# Candunio.net
KiCad netlist of a schematic drawn in Altium Designer
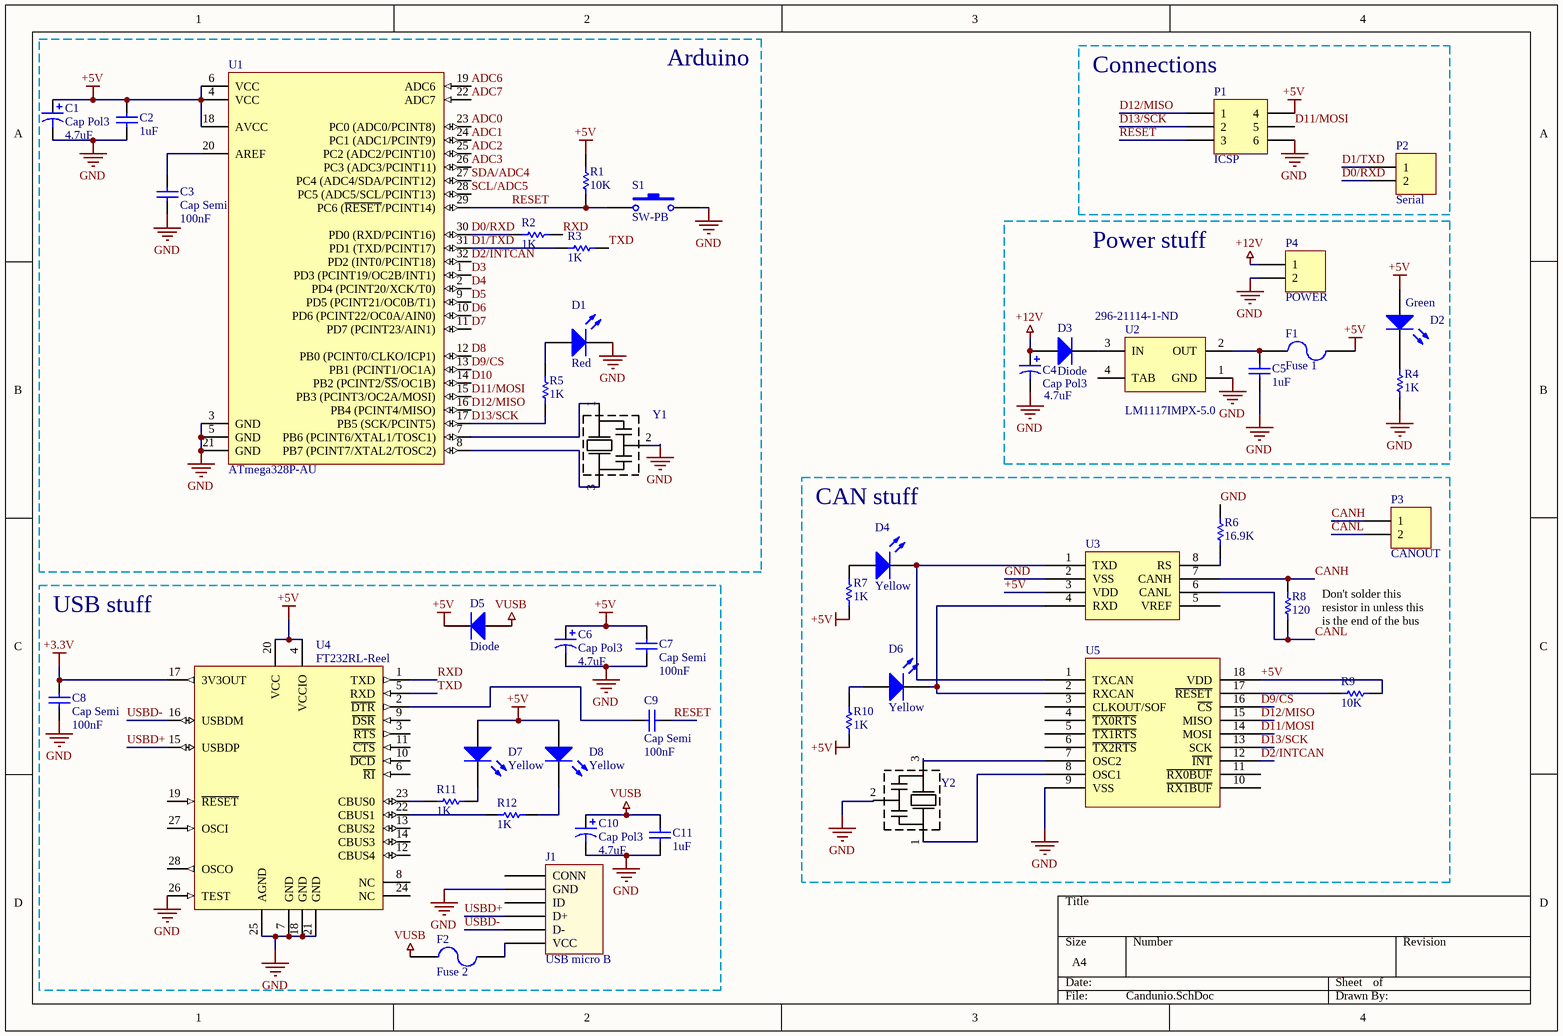
[diagram p0: Candunio.SchDoc]

(export (version "E")
  (design (tool "Eeschema 10.0.6"))
  (components
    (comp (ref "C1")
      (value "Cap Pol3")
      (footprint "CAPC3216X170N")
      (description "Polarized Capacitor (Surface Mount)")
      (fields
        (field (name "ALTIUM_VALUE") "4.7uF")
        (field (name "MANUFACTURER") "Kyocera AVX")
        (field (name "MANUFACTURER PART NUMBER") "12063C475KAT2A")
        (field (name "PUBLISHER") "Altium Limited")
      )
      (libsource (lib "Miscellaneous Devices") (part "Cap Pol3"))
    )
    (comp (ref "C2")
      (value "1uF")
      (footprint "CAPC3216X170N")
      (description "Capacitor (Semiconductor SIM Model)")
      (fields
        (field (name "MANUFACTURER") "Murata")
        (field (name "MANUFACTURER PART NUMBER") "GRM31MR71H105KA88L")
        (field (name "PUBLISHER") "Altium Limited")
      )
      (libsource (lib "Miscellaneous Devices") (part "Cap Semi"))
    )
    (comp (ref "C3")
      (value "Cap Semi")
      (footprint "CAPC3216X170N")
      (description "Capacitor (Semiconductor SIM Model)")
      (fields
        (field (name "ALTIUM_VALUE") "100nF")
        (field (name "MANUFACTURER") "Yageo")
        (field (name "MANUFACTURER PART NUMBER") "CC1206KKX7R0BB104")
        (field (name "PUBLISHER") "Altium Limited")
      )
      (libsource (lib "Miscellaneous Devices") (part "Cap Semi"))
    )
    (comp (ref "C4")
      (value "Cap Pol3")
      (footprint "CAPC3216X170N")
      (description "Polarized Capacitor (Surface Mount)")
      (fields
        (field (name "ALTIUM_VALUE") "4.7uF")
        (field (name "MANUFACTURER") "Kyocera AVX")
        (field (name "MANUFACTURER PART NUMBER") "12063C475KAT2A")
        (field (name "PUBLISHER") "Altium Limited")
      )
      (libsource (lib "Miscellaneous Devices") (part "Cap Pol3"))
    )
    (comp (ref "C5")
      (value "1uF")
      (footprint "CAPC3216X170N")
      (description "Capacitor (Semiconductor SIM Model)")
      (fields
        (field (name "MANUFACTURER") "Murata")
        (field (name "MANUFACTURER PART NUMBER") "GRM31MR71H105KA88L")
        (field (name "PUBLISHER") "Altium Limited")
      )
      (libsource (lib "Miscellaneous Devices") (part "Cap Semi"))
    )
    (comp (ref "C6")
      (value "Cap Pol3")
      (footprint "CAPC3216X170N")
      (description "Polarized Capacitor (Surface Mount)")
      (fields
        (field (name "ALTIUM_VALUE") "4.7uF")
        (field (name "MANUFACTURER") "Kyocera AVX")
        (field (name "MANUFACTURER PART NUMBER") "12063C475KAT2A")
        (field (name "PUBLISHER") "Altium Limited")
      )
      (libsource (lib "Miscellaneous Devices") (part "Cap Pol3"))
    )
    (comp (ref "C7")
      (value "Cap Semi")
      (footprint "CAPC3216X170N")
      (description "Capacitor (Semiconductor SIM Model)")
      (fields
        (field (name "ALTIUM_VALUE") "100nF")
        (field (name "MANUFACTURER") "Yageo")
        (field (name "MANUFACTURER PART NUMBER") "CC1206KKX7R0BB104")
        (field (name "PUBLISHER") "Altium Limited")
      )
      (libsource (lib "Miscellaneous Devices") (part "Cap Semi"))
    )
    (comp (ref "C8")
      (value "Cap Semi")
      (footprint "CAPC3216X170N")
      (description "Capacitor (Semiconductor SIM Model)")
      (fields
        (field (name "ALTIUM_VALUE") "100nF")
        (field (name "MANUFACTURER") "Yageo")
        (field (name "MANUFACTURER PART NUMBER") "CC1206KKX7R0BB104")
        (field (name "PUBLISHER") "Altium Limited")
      )
      (libsource (lib "Miscellaneous Devices") (part "Cap Semi"))
    )
    (comp (ref "C9")
      (value "Cap Semi")
      (footprint "CAPC3216X170N")
      (description "Capacitor (Semiconductor SIM Model)")
      (fields
        (field (name "ALTIUM_VALUE") "100nF")
        (field (name "MANUFACTURER") "Yageo")
        (field (name "MANUFACTURER PART NUMBER") "CC1206KKX7R0BB104")
        (field (name "PUBLISHER") "Altium Limited")
      )
      (libsource (lib "Miscellaneous Devices") (part "Cap Semi"))
    )
    (comp (ref "C10")
      (value "Cap Pol3")
      (footprint "CAPC3216X170N")
      (description "Polarized Capacitor (Surface Mount)")
      (fields
        (field (name "ALTIUM_VALUE") "4.7uF")
        (field (name "MANUFACTURER") "Kyocera AVX")
        (field (name "MANUFACTURER PART NUMBER") "12063C475KAT2A")
        (field (name "PUBLISHER") "Altium Limited")
      )
      (libsource (lib "Miscellaneous Devices") (part "Cap Pol3"))
    )
    (comp (ref "C11")
      (value "1uF")
      (footprint "CAPC3216X170N")
      (description "Capacitor (Semiconductor SIM Model)")
      (fields
        (field (name "MANUFACTURER") "Murata")
        (field (name "MANUFACTURER PART NUMBER") "GRM31MR71H105KA88L")
        (field (name "PUBLISHER") "Altium Limited")
      )
      (libsource (lib "Miscellaneous Devices") (part "Cap Semi"))
    )
    (comp (ref "D1")
      (value "Red")
      (footprint "LEDC3216X120NRED")
      (description "Typical RED, GREEN, YELLOW, AMBER GaAs LED")
      (fields
        (field (name "MANUFACTURER") "Broadcom Avago")
        (field (name "MANUFACTURER PART NUMBER") "HSMY-C150")
        (field (name "PUBLISHER") "Altium Limited")
      )
      (libsource (lib "Miscellaneous Devices") (part "LED2"))
    )
    (comp (ref "D2")
      (value "Green")
      (footprint "LEDC3216X120NGRN")
      (description "Typical RED, GREEN, YELLOW, AMBER GaAs LED")
      (fields
        (field (name "MANUFACTURER") "Broadcom Avago")
        (field (name "MANUFACTURER PART NUMBER") "HSMG-C150")
        (field (name "PUBLISHER") "Altium Limited")
      )
      (libsource (lib "Miscellaneous Devices") (part "LED2"))
    )
    (comp (ref "D3")
      (value "Diode")
      (footprint "DO-220AA")
      (description "Default Diode")
      (fields (field (name "PUBLISHER") "Altium Limited"))
      (libsource (lib "Miscellaneous Devices") (part "Diode"))
    )
    (comp (ref "D4")
      (value "Yellow")
      (footprint "LEDC3216X120NYEL")
      (description "Typical RED, GREEN, YELLOW, AMBER GaAs LED")
      (fields
        (field (name "MANUFACTURER") "Broadcom Avago")
        (field (name "MANUFACTURER PART NUMBER") "HSMY-C150")
        (field (name "PUBLISHER") "Altium Limited")
      )
      (libsource (lib "Miscellaneous Devices") (part "LED2"))
    )
    (comp (ref "D5")
      (value "Diode")
      (footprint "DO-220AA")
      (description "Default Diode")
      (fields (field (name "PUBLISHER") "Altium Limited"))
      (libsource (lib "Miscellaneous Devices") (part "Diode"))
    )
    (comp (ref "D6")
      (value "Yellow")
      (footprint "LEDC3216X120NYEL")
      (description "Typical RED, GREEN, YELLOW, AMBER GaAs LED")
      (fields
        (field (name "MANUFACTURER") "Broadcom Avago")
        (field (name "MANUFACTURER PART NUMBER") "HSMY-C150")
        (field (name "PUBLISHER") "Altium Limited")
      )
      (libsource (lib "Miscellaneous Devices") (part "LED2"))
    )
    (comp (ref "D7")
      (value "Yellow")
      (footprint "LEDC3216X120NYEL")
      (description "Typical RED, GREEN, YELLOW, AMBER GaAs LED")
      (fields
        (field (name "MANUFACTURER") "Broadcom Avago")
        (field (name "MANUFACTURER PART NUMBER") "HSMY-C150")
        (field (name "PUBLISHER") "Altium Limited")
      )
      (libsource (lib "Miscellaneous Devices") (part "LED2"))
    )
    (comp (ref "D8")
      (value "Yellow")
      (footprint "LEDC3216X120NYEL")
      (description "Typical RED, GREEN, YELLOW, AMBER GaAs LED")
      (fields
        (field (name "MANUFACTURER") "Broadcom Avago")
        (field (name "MANUFACTURER PART NUMBER") "HSMY-C150")
        (field (name "PUBLISHER") "Altium Limited")
      )
      (libsource (lib "Miscellaneous Devices") (part "LED2"))
    )
    (comp (ref "F1")
      (value "Fuse 1")
      (footprint "FUSC4632X85N")
      (description "Fuse")
      (fields
        (field (name "PART NUMBER") "MF-MSMF050-2")
        (field (name "MANUFACTURER") "Bourns")
        (field (name "PUBLISHER") "Altium Limited")
      )
      (libsource (lib "Miscellaneous Devices") (part "Fuse 2"))
    )
    (comp (ref "F2")
      (value "Fuse 2")
      (footprint "FUSC4632X85N")
      (description "Fuse")
      (fields
        (field (name "PART NUMBER") "MF-MSMF050-2")
        (field (name "MANUFACTURER") "Bourns")
        (field (name "PUBLISHER") "Altium Limited")
      )
      (libsource (lib "Miscellaneous Devices") (part "Fuse 2"))
    )
    (comp (ref "J1")
      (value "USB micro B")
      (footprint "1050170001")
      (description "CONN SM TH USB MICRO MODIFIED FOR DRILL")
      (fields (field (name "PART NUMBER") "WM1399CT-ND"))
      (libsource (lib "electronpowered") (part "1050170001"))
    )
    (comp (ref "P1")
      (value "ICSP")
      (footprint "Pin Header 2x3 TH Pitch 2.54mm")
      (description "Header, 3-Pin, Dual row")
      (fields (field (name "PUBLISHER") "Altium Limited"))
      (libsource (lib "Miscellaneous Connectors") (part "Header 3X2A"))
    )
    (comp (ref "P2")
      (value "Serial")
      (footprint "Candunio:Pin Header 1x2 TH Pitch 2.54mm")
      (description "Header, 2-Pin")
      (fields (field (name "PUBLISHER") "Altium Limited"))
      (libsource (lib "Miscellaneous Connectors") (part "Header 2"))
    )
    (comp (ref "P3")
      (value "CANOUT")
      (footprint "Candunio:Pin Header 1x2 TH Pitch 2.54mm")
      (description "Header, 2-Pin")
      (fields (field (name "PUBLISHER") "Altium Limited"))
      (libsource (lib "Miscellaneous Connectors") (part "Header 2"))
    )
    (comp (ref "P4")
      (value "POWER")
      (footprint "Candunio:Pin Header 1x2 TH Pitch 2.54mm")
      (description "Header, 2-Pin")
      (fields (field (name "PUBLISHER") "Altium Limited"))
      (libsource (lib "Miscellaneous Connectors") (part "Header 2"))
    )
    (comp (ref "R1")
      (value "10K")
      (footprint "RESC3216X60N")
      (description "Resistor")
      (fields
        (field (name "MANUFACTURER") "Stackpole Electronics")
        (field (name "MANUFACTURER PART NUMBER") "RNCP1206FTD1K00")
      )
      (libsource (lib "Miscellaneous Devices") (part "Res1"))
    )
    (comp (ref "R2")
      (value "1K")
      (footprint "RESC3216X60N")
      (description "Resistor")
      (fields
        (field (name "MANUFACTURER") "Stackpole Electronics")
        (field (name "MANUFACTURER PART NUMBER") "RNCP1206FTD1K00")
      )
      (libsource (lib "Miscellaneous Devices") (part "Res1"))
    )
    (comp (ref "R3")
      (value "1K")
      (footprint "RESC3216X60N")
      (description "Resistor")
      (fields
        (field (name "MANUFACTURER") "Stackpole Electronics")
        (field (name "MANUFACTURER PART NUMBER") "RNCP1206FTD1K00")
      )
      (libsource (lib "Miscellaneous Devices") (part "Res1"))
    )
    (comp (ref "R4")
      (value "1K")
      (footprint "RESC3216X60N")
      (description "Resistor")
      (fields
        (field (name "MANUFACTURER") "Stackpole Electronics")
        (field (name "MANUFACTURER PART NUMBER") "RNCP1206FTD1K00")
      )
      (libsource (lib "Miscellaneous Devices") (part "Res1"))
    )
    (comp (ref "R5")
      (value "1K")
      (footprint "RESC3216X60N")
      (description "Resistor")
      (fields
        (field (name "MANUFACTURER") "Stackpole Electronics")
        (field (name "MANUFACTURER PART NUMBER") "RNCP1206FTD1K00")
      )
      (libsource (lib "Miscellaneous Devices") (part "Res1"))
    )
    (comp (ref "R6")
      (value "16.9K")
      (footprint "RESC3216X60N")
      (description "Resistor")
      (fields
        (field (name "MANUFACTURER") "TE Connectivity Holsworthy")
        (field (name "MANUFACTURER PART NUMBER") "CRGH1206F16K9")
      )
      (libsource (lib "Miscellaneous Devices") (part "Res1"))
    )
    (comp (ref "R7")
      (value "1K")
      (footprint "RESC3216X60N")
      (description "Resistor")
      (fields
        (field (name "MANUFACTURER") "Stackpole Electronics")
        (field (name "MANUFACTURER PART NUMBER") "RNCP1206FTD1K00")
      )
      (libsource (lib "Miscellaneous Devices") (part "Res1"))
    )
    (comp (ref "R8")
      (value "120")
      (footprint "RESC3216X60N")
      (description "Resistor")
      (fields
        (field (name "MANUFACTURER") "Vishay")
        (field (name "MANUFACTURER PART NUMBER") "CRCW1206120RFKEAHP")
      )
      (libsource (lib "Miscellaneous Devices") (part "Res1"))
    )
    (comp (ref "R9")
      (value "10K")
      (footprint "RESC3216X60N")
      (description "Resistor")
      (fields
        (field (name "MANUFACTURER") "Stackpole Electronics")
        (field (name "MANUFACTURER PART NUMBER") "RNCP1206FTD10K0")
      )
      (libsource (lib "Miscellaneous Devices") (part "Res1"))
    )
    (comp (ref "R10")
      (value "1K")
      (footprint "RESC3216X60N")
      (description "Resistor")
      (fields
        (field (name "MANUFACTURER") "Stackpole Electronics")
        (field (name "MANUFACTURER PART NUMBER") "RNCP1206FTD1K00")
      )
      (libsource (lib "Miscellaneous Devices") (part "Res1"))
    )
    (comp (ref "R11")
      (value "1K")
      (footprint "RESC3216X60N")
      (description "Resistor")
      (fields
        (field (name "MANUFACTURER") "Stackpole Electronics")
        (field (name "MANUFACTURER PART NUMBER") "RNCP1206FTD1K00")
      )
      (libsource (lib "Miscellaneous Devices") (part "Res1"))
    )
    (comp (ref "R12")
      (value "1K")
      (footprint "RESC3216X60N")
      (description "Resistor")
      (fields
        (field (name "MANUFACTURER") "Stackpole Electronics")
        (field (name "MANUFACTURER PART NUMBER") "RNCP1206FTD1K00")
      )
      (libsource (lib "Miscellaneous Devices") (part "Res1"))
    )
    (comp (ref "S1")
      (value "SW-PB")
      (footprint "C1206")
      (description "Switch")
      (fields
        (field (name "MANUFACTURER") "ITT C&K")
        (field (name "MANUFACTURER PART NUMBER") "KXT331LHS")
        (field (name "PUBLISHER") "Altium Limited")
      )
      (libsource (lib "Miscellaneous Devices") (part "SW-PB"))
    )
    (comp (ref "U1")
      (value "ATmega328P-AU")
      (footprint "QFP80P900X900X120-32N")
      (fields (field (name "PUBLISHER") "Altium Limited"))
      (libsource (lib "Atmel Microcontroller 8-Bit megaAVR") (part "ATmega328P-AU"))
    )
    (comp (ref "U2")
      (value "LM1117IMPX-5.0")
      (footprint "SOT230P700X180-4N")
      (description "800mA Low-Dropout Linear Regulator, 4-pin SOT-223")
      (fields
        (field (name "PARTNUMBER") "LM1117IMPX-5.0/NOPBCT-ND")
        (field (name "MANUFACTURER") "National Semiconductor")
        (field (name "SUPPLIER PART NUMBER") "296-21114-1-ND")
        (field (name "PUBLISHER") "Altium Limited")
      )
      (libsource (lib "NSC LDO") (part "LM1117IMPX-5.0"))
    )
    (comp (ref "U3")
      (value "MCP2551-E/SN")
      (footprint "SOIC127P600X175-8N")
      (description "SOIC")
      (libsource (lib "AMSComponents") (part "MCP2551-E/SN"))
    )
    (comp (ref "U4")
      (value "FT232RL-Reel")
      (footprint "SOP65P780X200-28N")
      (description "USB UART Asynchronous Serial Data Transfer Chip, SSOP-28, Tape and Reel")
      (fields
        (field (name "MANUFACTURER") "FTDI")
        (field (name "MANUFACTURER PART NUMBER") "FT232RL-REEL")
        (field (name "PUBLISHER") "Altium Limited")
      )
      (libsource (lib "FTDI Communication UART") (part "FT232RL-Reel"))
    )
    (comp (ref "U5")
      (value "MCP2515-E/ST")
      (footprint "SOIC127P1030X265-18N")
      (description "SOIC")
      (libsource (lib "AMSComponents") (part "MCP2515-E/ST"))
    )
    (comp (ref "Y1")
      (value "CSTCE16M0V53-R0")
      (footprint "CSTCE_G")
      (fields
        (field (name "MANUFACTURER") "Murata")
        (field (name "MANUFACTURER PART NUMBER") "CSTCE16M0V53C-R0")
        (field (name "TOLERANCE") "0.5%")
      )
      (libsource (lib "AMSComponents") (part "CSTCE16M0V53-R0"))
    )
    (comp (ref "Y2")
      (value "CSTCE16M0V53-R0")
      (footprint "CSTCE_G")
      (fields
        (field (name "MANUFACTURER") "Murata")
        (field (name "MANUFACTURER PART NUMBER") "CSTCE16M0V53C-R0")
        (field (name "TOLERANCE") "0.5%")
      )
      (libsource (lib "AMSComponents") (part "CSTCE16M0V53-R0"))
    )
  )
  (nets
    (net (code "1") (name "+3.3V") (class "Default")
      (node (ref "C8") (pin "1") (pinfunction "1_1") (pintype "passive"))
      (node (ref "U4") (pin "17") (pinfunction "3V3OUT_17") (pintype "output"))
    )
    (net (code "2") (name "+5V") (class "Default")
      (node (ref "C1") (pin "1") (pinfunction "1_1") (pintype "passive"))
      (node (ref "C2") (pin "1") (pinfunction "1_1") (pintype "passive"))
      (node (ref "C6") (pin "1") (pinfunction "1_1") (pintype "passive"))
      (node (ref "C7") (pin "1") (pinfunction "1_1") (pintype "passive"))
      (node (ref "D2") (pin "1") (pinfunction "A_1") (pintype "passive"))
      (node (ref "D5") (pin "1") (pinfunction "K_1") (pintype "passive"))
      (node (ref "D7") (pin "1") (pinfunction "A_1") (pintype "passive"))
      (node (ref "D8") (pin "1") (pinfunction "A_1") (pintype "passive"))
      (node (ref "F1") (pin "2") (pinfunction "2_2") (pintype "passive"))
      (node (ref "P1") (pin "4") (pinfunction "4_4") (pintype "passive"))
      (node (ref "R1") (pin "1") (pinfunction "1_1") (pintype "passive"))
      (node (ref "R10") (pin "2") (pinfunction "2_2") (pintype "passive"))
      (node (ref "R7") (pin "1") (pinfunction "1_1") (pintype "passive"))
      (node (ref "R9") (pin "2") (pinfunction "2_2") (pintype "passive"))
      (node (ref "U1") (pin "18") (pinfunction "AVCC_18") (pintype "power_in"))
      (node (ref "U1") (pin "4") (pinfunction "VCC_4") (pintype "power_in"))
      (node (ref "U1") (pin "6") (pinfunction "VCC_6") (pintype "power_in"))
      (node (ref "U3") (pin "3") (pinfunction "VDD_3") (pintype "passive"))
      (node (ref "U4") (pin "20") (pinfunction "VCC_20") (pintype "power_in"))
      (node (ref "U4") (pin "4") (pinfunction "VCCIO_4") (pintype "power_in"))
      (node (ref "U5") (pin "18") (pinfunction "VDD_18") (pintype "passive"))
    )
    (net (code "3") (name "+12V") (class "Default")
      (node (ref "C4") (pin "1") (pinfunction "1_1") (pintype "passive"))
      (node (ref "D3") (pin "2") (pinfunction "A_2") (pintype "passive"))
      (node (ref "P4") (pin "1") (pinfunction "1_1") (pintype "passive"))
    )
    (net (code "4") (name "/ADC0") (class "Default")
      (node (ref "U1") (pin "23") (pinfunction "PC0_(ADC0/PCINT8)_23") (pintype "bidirectional"))
    )
    (net (code "5") (name "/ADC1") (class "Default")
      (node (ref "U1") (pin "24") (pinfunction "PC1_(ADC1/PCINT9)_24") (pintype "bidirectional"))
    )
    (net (code "6") (name "/ADC2") (class "Default")
      (node (ref "U1") (pin "25") (pinfunction "PC2_(ADC2/PCINT10)_25") (pintype "bidirectional"))
    )
    (net (code "7") (name "/ADC3") (class "Default")
      (node (ref "U1") (pin "26") (pinfunction "PC3_(ADC3/PCINT11)_26") (pintype "bidirectional"))
    )
    (net (code "8") (name "/ADC6") (class "Default")
      (node (ref "U1") (pin "19") (pinfunction "ADC6_19") (pintype "input"))
    )
    (net (code "9") (name "/ADC7") (class "Default")
      (node (ref "U1") (pin "22") (pinfunction "ADC7_22") (pintype "input"))
    )
    (net (code "10") (name "/CANH") (class "Default")
      (node (ref "P3") (pin "1") (pinfunction "1_1") (pintype "passive"))
      (node (ref "R8") (pin "1") (pinfunction "1_1") (pintype "passive"))
      (node (ref "U3") (pin "7") (pinfunction "CANH_7") (pintype "passive"))
    )
    (net (code "11") (name "/CANL") (class "Default")
      (node (ref "P3") (pin "2") (pinfunction "2_2") (pintype "passive"))
      (node (ref "R8") (pin "2") (pinfunction "2_2") (pintype "passive"))
      (node (ref "U3") (pin "6") (pinfunction "CANL_6") (pintype "passive"))
    )
    (net (code "12") (name "/D0{slash}RXD") (class "Default")
      (node (ref "P2") (pin "2") (pinfunction "2_2") (pintype "passive"))
      (node (ref "R2") (pin "1") (pinfunction "1_1") (pintype "passive"))
      (node (ref "U1") (pin "30") (pinfunction "PD0_(RXD/PCINT16)_30") (pintype "bidirectional"))
    )
    (net (code "13") (name "/D1{slash}TXD") (class "Default")
      (node (ref "P2") (pin "1") (pinfunction "1_1") (pintype "passive"))
      (node (ref "R3") (pin "1") (pinfunction "1_1") (pintype "passive"))
      (node (ref "U1") (pin "31") (pinfunction "PD1_(TXD/PCINT17)_31") (pintype "bidirectional"))
    )
    (net (code "14") (name "/D2{slash}INTCAN") (class "Default")
      (node (ref "U1") (pin "32") (pinfunction "PD2_(INT0/PCINT18)_32") (pintype "bidirectional"))
      (node (ref "U5") (pin "12") (pinfunction "~{INT}_12") (pintype "passive"))
    )
    (net (code "15") (name "/D3") (class "Default")
      (node (ref "U1") (pin "1") (pinfunction "PD3_(PCINT19/OC2B/INT1)_1") (pintype "bidirectional"))
    )
    (net (code "16") (name "/D4") (class "Default")
      (node (ref "U1") (pin "2") (pinfunction "PD4_(PCINT20/XCK/T0)_2") (pintype "bidirectional"))
    )
    (net (code "17") (name "/D5") (class "Default")
      (node (ref "U1") (pin "9") (pinfunction "PD5_(PCINT21/OC0B/T1)_9") (pintype "bidirectional"))
    )
    (net (code "18") (name "/D6") (class "Default")
      (node (ref "U1") (pin "10") (pinfunction "PD6_(PCINT22/OC0A/AIN0)_10") (pintype "bidirectional"))
    )
    (net (code "19") (name "/D7") (class "Default")
      (node (ref "U1") (pin "11") (pinfunction "PD7_(PCINT23/AIN1)_11") (pintype "bidirectional"))
    )
    (net (code "20") (name "/D8") (class "Default")
      (node (ref "U1") (pin "12") (pinfunction "PB0_(PCINT0/CLKO/ICP1)_12") (pintype "bidirectional"))
    )
    (net (code "21") (name "/D9{slash}CS") (class "Default")
      (node (ref "U1") (pin "13") (pinfunction "PB1_(PCINT1/OC1A)_13") (pintype "bidirectional"))
      (node (ref "U5") (pin "16") (pinfunction "~{CS}_16") (pintype "passive"))
    )
    (net (code "22") (name "/D10") (class "Default")
      (node (ref "U1") (pin "14") (pinfunction "PB2_(PCINT2/~{SS}/OC1B)_14") (pintype "bidirectional"))
    )
    (net (code "23") (name "/D11{slash}MOSI") (class "Default")
      (node (ref "P1") (pin "5") (pinfunction "5_5") (pintype "passive"))
      (node (ref "U1") (pin "15") (pinfunction "PB3_(PCINT3/OC2A/MOSI)_15") (pintype "bidirectional"))
      (node (ref "U5") (pin "14") (pinfunction "MOSI_14") (pintype "passive"))
    )
    (net (code "24") (name "/D12{slash}MISO") (class "Default")
      (node (ref "P1") (pin "1") (pinfunction "1_1") (pintype "passive"))
      (node (ref "U1") (pin "16") (pinfunction "PB4_(PCINT4/MISO)_16") (pintype "bidirectional"))
      (node (ref "U5") (pin "15") (pinfunction "MISO_15") (pintype "passive"))
    )
    (net (code "25") (name "/D13{slash}SCK") (class "Default")
      (node (ref "P1") (pin "2") (pinfunction "2_2") (pintype "passive"))
      (node (ref "R5") (pin "2") (pinfunction "2_2") (pintype "passive"))
      (node (ref "U1") (pin "17") (pinfunction "PB5_(SCK/PCINT5)_17") (pintype "bidirectional"))
      (node (ref "U5") (pin "13") (pinfunction "SCK_13") (pintype "passive"))
    )
    (net (code "26") (name "/RESET") (class "Default")
      (node (ref "C9") (pin "1") (pinfunction "1_1") (pintype "passive"))
      (node (ref "P1") (pin "3") (pinfunction "3_3") (pintype "passive"))
      (node (ref "R1") (pin "2") (pinfunction "2_2") (pintype "passive"))
      (node (ref "S1") (pin "1") (pinfunction "1_1") (pintype "passive"))
      (node (ref "U1") (pin "29") (pinfunction "PC6_(~{RESET}/PCINT14)_29") (pintype "bidirectional"))
    )
    (net (code "27") (name "/RXD") (class "Default")
      (node (ref "R2") (pin "2") (pinfunction "2_2") (pintype "passive"))
      (node (ref "U4") (pin "1") (pinfunction "TXD_1") (pintype "output"))
    )
    (net (code "28") (name "/SCL{slash}ADC5") (class "Default")
      (node (ref "U1") (pin "28") (pinfunction "PC5_(ADC5/SCL/PCINT13)_28") (pintype "bidirectional"))
    )
    (net (code "29") (name "/SDA{slash}ADC4") (class "Default")
      (node (ref "U1") (pin "27") (pinfunction "PC4_(ADC4/SDA/PCINT12)_27") (pintype "bidirectional"))
    )
    (net (code "30") (name "/TXD") (class "Default")
      (node (ref "R3") (pin "2") (pinfunction "2_2") (pintype "passive"))
      (node (ref "U4") (pin "5") (pinfunction "RXD_5") (pintype "input"))
    )
    (net (code "31") (name "/USBD+") (class "Default")
      (node (ref "J1") (pin "3") (pinfunction "D+_3") (pintype "passive"))
      (node (ref "U4") (pin "15") (pinfunction "USBDP_15") (pintype "bidirectional"))
    )
    (net (code "32") (name "/USBD-") (class "Default")
      (node (ref "J1") (pin "2") (pinfunction "D-_2") (pintype "passive"))
      (node (ref "U4") (pin "16") (pinfunction "USBDM_16") (pintype "bidirectional"))
    )
    (net (code "33") (name "GND") (class "Default")
      (node (ref "C1") (pin "2") (pinfunction "2_2") (pintype "passive"))
      (node (ref "C10") (pin "2") (pinfunction "2_2") (pintype "passive"))
      (node (ref "C11") (pin "2") (pinfunction "2_2") (pintype "passive"))
      (node (ref "C2") (pin "2") (pinfunction "2_2") (pintype "passive"))
      (node (ref "C3") (pin "2") (pinfunction "2_2") (pintype "passive"))
      (node (ref "C4") (pin "2") (pinfunction "2_2") (pintype "passive"))
      (node (ref "C5") (pin "1") (pinfunction "1_1") (pintype "passive"))
      (node (ref "C6") (pin "2") (pinfunction "2_2") (pintype "passive"))
      (node (ref "C7") (pin "2") (pinfunction "2_2") (pintype "passive"))
      (node (ref "C8") (pin "2") (pinfunction "2_2") (pintype "passive"))
      (node (ref "D1") (pin "2") (pinfunction "K_2") (pintype "passive"))
      (node (ref "J1") (pin "5") (pinfunction "GND_5") (pintype "passive"))
      (node (ref "P1") (pin "6") (pinfunction "6_6") (pintype "passive"))
      (node (ref "P4") (pin "2") (pinfunction "2_2") (pintype "passive"))
      (node (ref "R4") (pin "2") (pinfunction "2_2") (pintype "passive"))
      (node (ref "R6") (pin "1") (pinfunction "1_1") (pintype "passive"))
      (node (ref "S1") (pin "2") (pinfunction "2_2") (pintype "passive"))
      (node (ref "U1") (pin "21") (pinfunction "GND_21") (pintype "power_in"))
      (node (ref "U1") (pin "3") (pinfunction "GND_3") (pintype "power_in"))
      (node (ref "U1") (pin "5") (pinfunction "GND_5") (pintype "power_in"))
      (node (ref "U2") (pin "1") (pinfunction "GND_1") (pintype "power_in"))
      (node (ref "U3") (pin "2") (pinfunction "VSS_2") (pintype "passive"))
      (node (ref "U4") (pin "18") (pinfunction "GND_18") (pintype "power_in"))
      (node (ref "U4") (pin "21") (pinfunction "GND_21") (pintype "power_in"))
      (node (ref "U4") (pin "25") (pinfunction "AGND_25") (pintype "power_in"))
      (node (ref "U4") (pin "26") (pinfunction "TEST_26") (pintype "input"))
      (node (ref "U4") (pin "7") (pinfunction "GND_7") (pintype "power_in"))
      (node (ref "U5") (pin "9") (pinfunction "VSS_9") (pintype "passive"))
      (node (ref "Y1") (pin "2") (pinfunction "2_2") (pintype "passive"))
      (node (ref "Y2") (pin "2") (pinfunction "2_2") (pintype "passive"))
    )
    (net (code "34") (name "Net-(D1-A)") (class "Default")
      (node (ref "D1") (pin "1") (pinfunction "A_1") (pintype "passive"))
      (node (ref "R5") (pin "1") (pinfunction "1_1") (pintype "passive"))
    )
    (net (code "35") (name "Net-(D2-K)") (class "Default")
      (node (ref "D2") (pin "2") (pinfunction "K_2") (pintype "passive"))
      (node (ref "R4") (pin "1") (pinfunction "1_1") (pintype "passive"))
    )
    (net (code "36") (name "Net-(D3-K)") (class "Default")
      (node (ref "D3") (pin "1") (pinfunction "K_1") (pintype "passive"))
      (node (ref "U2") (pin "3") (pinfunction "IN_3") (pintype "power_in"))
    )
    (net (code "37") (name "Net-(D4-A)") (class "Default")
      (node (ref "D4") (pin "1") (pinfunction "A_1") (pintype "passive"))
      (node (ref "R7") (pin "2") (pinfunction "2_2") (pintype "passive"))
    )
    (net (code "38") (name "Net-(D4-K)") (class "Default")
      (node (ref "D4") (pin "2") (pinfunction "K_2") (pintype "passive"))
      (node (ref "U3") (pin "1") (pinfunction "TXD_1") (pintype "passive"))
      (node (ref "U5") (pin "1") (pinfunction "TXCAN_1") (pintype "passive"))
    )
    (net (code "39") (name "Net-(D6-A)") (class "Default")
      (node (ref "D6") (pin "1") (pinfunction "A_1") (pintype "passive"))
      (node (ref "R10") (pin "1") (pinfunction "1_1") (pintype "passive"))
    )
    (net (code "40") (name "Net-(D6-K)") (class "Default")
      (node (ref "D6") (pin "2") (pinfunction "K_2") (pintype "passive"))
      (node (ref "U3") (pin "4") (pinfunction "RXD_4") (pintype "passive"))
      (node (ref "U5") (pin "2") (pinfunction "RXCAN_2") (pintype "passive"))
    )
    (net (code "41") (name "Net-(D7-K)") (class "Default")
      (node (ref "D7") (pin "2") (pinfunction "K_2") (pintype "passive"))
      (node (ref "R11") (pin "2") (pinfunction "2_2") (pintype "passive"))
    )
    (net (code "42") (name "Net-(D8-K)") (class "Default")
      (node (ref "D8") (pin "2") (pinfunction "K_2") (pintype "passive"))
      (node (ref "R12") (pin "2") (pinfunction "2_2") (pintype "passive"))
    )
    (net (code "43") (name "Net-(J1-VCC)") (class "Default")
      (node (ref "F2") (pin "2") (pinfunction "2_2") (pintype "passive"))
      (node (ref "J1") (pin "1") (pinfunction "VCC_1") (pintype "passive"))
    )
    (net (code "44") (name "Net-(U1-AREF)") (class "Default")
      (node (ref "C3") (pin "1") (pinfunction "1_1") (pintype "passive"))
      (node (ref "U1") (pin "20") (pinfunction "AREF_20") (pintype "passive"))
    )
    (net (code "45") (name "Net-(U1-PB6_(PCINT6{slash}XTAL1{slash}TOSC1))") (class "Default")
      (node (ref "U1") (pin "7") (pinfunction "PB6_(PCINT6/XTAL1/TOSC1)_7") (pintype "bidirectional"))
      (node (ref "Y1") (pin "1") (pinfunction "1_1") (pintype "passive"))
    )
    (net (code "46") (name "Net-(U1-PB7_(PCINT7{slash}XTAL2{slash}TOSC2))") (class "Default")
      (node (ref "U1") (pin "8") (pinfunction "PB7_(PCINT7/XTAL2/TOSC2)_8") (pintype "bidirectional"))
      (node (ref "Y1") (pin "3") (pinfunction "3_3") (pintype "passive"))
    )
    (net (code "47") (name "Net-(U2-OUT)") (class "Default")
      (node (ref "C5") (pin "2") (pinfunction "2_2") (pintype "passive"))
      (node (ref "F1") (pin "1") (pinfunction "1_1") (pintype "passive"))
      (node (ref "U2") (pin "2") (pinfunction "OUT_2") (pintype "power_in"))
    )
    (net (code "48") (name "Net-(U3-RS)") (class "Default")
      (node (ref "R6") (pin "2") (pinfunction "2_2") (pintype "passive"))
      (node (ref "U3") (pin "8") (pinfunction "RS_8") (pintype "passive"))
    )
    (net (code "49") (name "Net-(U4-CBUS0)") (class "Default")
      (node (ref "R11") (pin "1") (pinfunction "1_1") (pintype "passive"))
      (node (ref "U4") (pin "23") (pinfunction "CBUS0_23") (pintype "bidirectional"))
    )
    (net (code "50") (name "Net-(U4-CBUS1)") (class "Default")
      (node (ref "R12") (pin "1") (pinfunction "1_1") (pintype "passive"))
      (node (ref "U4") (pin "22") (pinfunction "CBUS1_22") (pintype "bidirectional"))
    )
    (net (code "51") (name "Net-(U4-~{DTR})") (class "Default")
      (node (ref "C9") (pin "2") (pinfunction "2_2") (pintype "passive"))
      (node (ref "U4") (pin "2") (pinfunction "~{DTR}_2") (pintype "output"))
    )
    (net (code "52") (name "Net-(U5-OSC1)") (class "Default")
      (node (ref "U5") (pin "8") (pinfunction "OSC1_8") (pintype "passive"))
      (node (ref "Y2") (pin "1") (pinfunction "1_1") (pintype "passive"))
    )
    (net (code "53") (name "Net-(U5-OSC2)") (class "Default")
      (node (ref "U5") (pin "7") (pinfunction "OSC2_7") (pintype "passive"))
      (node (ref "Y2") (pin "3") (pinfunction "3_3") (pintype "passive"))
    )
    (net (code "54") (name "Net-(U5-~{RESET})") (class "Default")
      (node (ref "R9") (pin "1") (pinfunction "1_1") (pintype "passive"))
      (node (ref "U5") (pin "17") (pinfunction "~{RESET}_17") (pintype "passive"))
    )
    (net (code "55") (name "VUSB") (class "Default")
      (node (ref "C10") (pin "1") (pinfunction "1_1") (pintype "passive"))
      (node (ref "C11") (pin "1") (pinfunction "1_1") (pintype "passive"))
      (node (ref "D5") (pin "2") (pinfunction "A_2") (pintype "passive"))
      (node (ref "F2") (pin "1") (pinfunction "1_1") (pintype "passive"))
    )
    (net (code "56") (name "unconnected-(J1-CONN-Pad0)") (class "Default")
      (node (ref "J1") (pin "0") (pinfunction "CONN_0") (pintype "passive"))
    )
    (net (code "57") (name "unconnected-(J1-ID-Pad4)") (class "Default")
      (node (ref "J1") (pin "4") (pinfunction "ID_4") (pintype "passive"))
    )
    (net (code "58") (name "unconnected-(U2-TAB-Pad4)") (class "Default")
      (node (ref "U2") (pin "4") (pinfunction "TAB_4") (pintype "power_in"))
    )
    (net (code "59") (name "unconnected-(U3-VREF-Pad5)") (class "Default")
      (node (ref "U3") (pin "5") (pinfunction "VREF_5") (pintype "passive"))
    )
    (net (code "60") (name "unconnected-(U4-CBUS2-Pad13)") (class "Default")
      (node (ref "U4") (pin "13") (pinfunction "CBUS2_13") (pintype "bidirectional"))
    )
    (net (code "61") (name "unconnected-(U4-CBUS3-Pad14)") (class "Default")
      (node (ref "U4") (pin "14") (pinfunction "CBUS3_14") (pintype "bidirectional"))
    )
    (net (code "62") (name "unconnected-(U4-CBUS4-Pad12)") (class "Default")
      (node (ref "U4") (pin "12") (pinfunction "CBUS4_12") (pintype "bidirectional"))
    )
    (net (code "63") (name "unconnected-(U4-NC-Pad8)") (class "Default")
      (node (ref "U4") (pin "8") (pinfunction "NC_8") (pintype "passive"))
    )
    (net (code "64") (name "unconnected-(U4-NC-Pad24)") (class "Default")
      (node (ref "U4") (pin "24") (pinfunction "NC_24") (pintype "passive"))
    )
    (net (code "65") (name "unconnected-(U4-OSCI-Pad27)") (class "Default")
      (node (ref "U4") (pin "27") (pinfunction "OSCI_27") (pintype "input"))
    )
    (net (code "66") (name "unconnected-(U4-OSCO-Pad28)") (class "Default")
      (node (ref "U4") (pin "28") (pinfunction "OSCO_28") (pintype "output"))
    )
    (net (code "67") (name "unconnected-(U4-~{CTS}-Pad11)") (class "Default")
      (node (ref "U4") (pin "11") (pinfunction "~{CTS}_11") (pintype "input"))
    )
    (net (code "68") (name "unconnected-(U4-~{DCD}-Pad10)") (class "Default")
      (node (ref "U4") (pin "10") (pinfunction "~{DCD}_10") (pintype "input"))
    )
    (net (code "69") (name "unconnected-(U4-~{DSR}-Pad9)") (class "Default")
      (node (ref "U4") (pin "9") (pinfunction "~{DSR}_9") (pintype "input"))
    )
    (net (code "70") (name "unconnected-(U4-~{RESET}-Pad19)") (class "Default")
      (node (ref "U4") (pin "19") (pinfunction "~{RESET}_19") (pintype "input"))
    )
    (net (code "71") (name "unconnected-(U4-~{RI}-Pad6)") (class "Default")
      (node (ref "U4") (pin "6") (pinfunction "~{RI}_6") (pintype "input"))
    )
    (net (code "72") (name "unconnected-(U4-~{RTS}-Pad3)") (class "Default")
      (node (ref "U4") (pin "3") (pinfunction "~{RTS}_3") (pintype "output"))
    )
    (net (code "73") (name "unconnected-(U5-CLKOUT{slash}SOF-Pad3)") (class "Default")
      (node (ref "U5") (pin "3") (pinfunction "CLKOUT/SOF_3") (pintype "passive"))
    )
    (net (code "74") (name "unconnected-(U5-~{RX0BUF}-Pad11)") (class "Default")
      (node (ref "U5") (pin "11") (pinfunction "~{RX0BUF}_11") (pintype "passive"))
    )
    (net (code "75") (name "unconnected-(U5-~{RX1BUF}-Pad10)") (class "Default")
      (node (ref "U5") (pin "10") (pinfunction "~{RX1BUF}_10") (pintype "passive"))
    )
    (net (code "76") (name "unconnected-(U5-~{TX0RTS}-Pad4)") (class "Default")
      (node (ref "U5") (pin "4") (pinfunction "~{TX0RTS}_4") (pintype "passive"))
    )
    (net (code "77") (name "unconnected-(U5-~{TX1RTS}-Pad5)") (class "Default")
      (node (ref "U5") (pin "5") (pinfunction "~{TX1RTS}_5") (pintype "passive"))
    )
    (net (code "78") (name "unconnected-(U5-~{TX2RTS}-Pad6)") (class "Default")
      (node (ref "U5") (pin "6") (pinfunction "~{TX2RTS}_6") (pintype "passive"))
    )
  )
)
